# Battery_and_Charging.net
KiCad netlist of a schematic drawn in Altium Designer
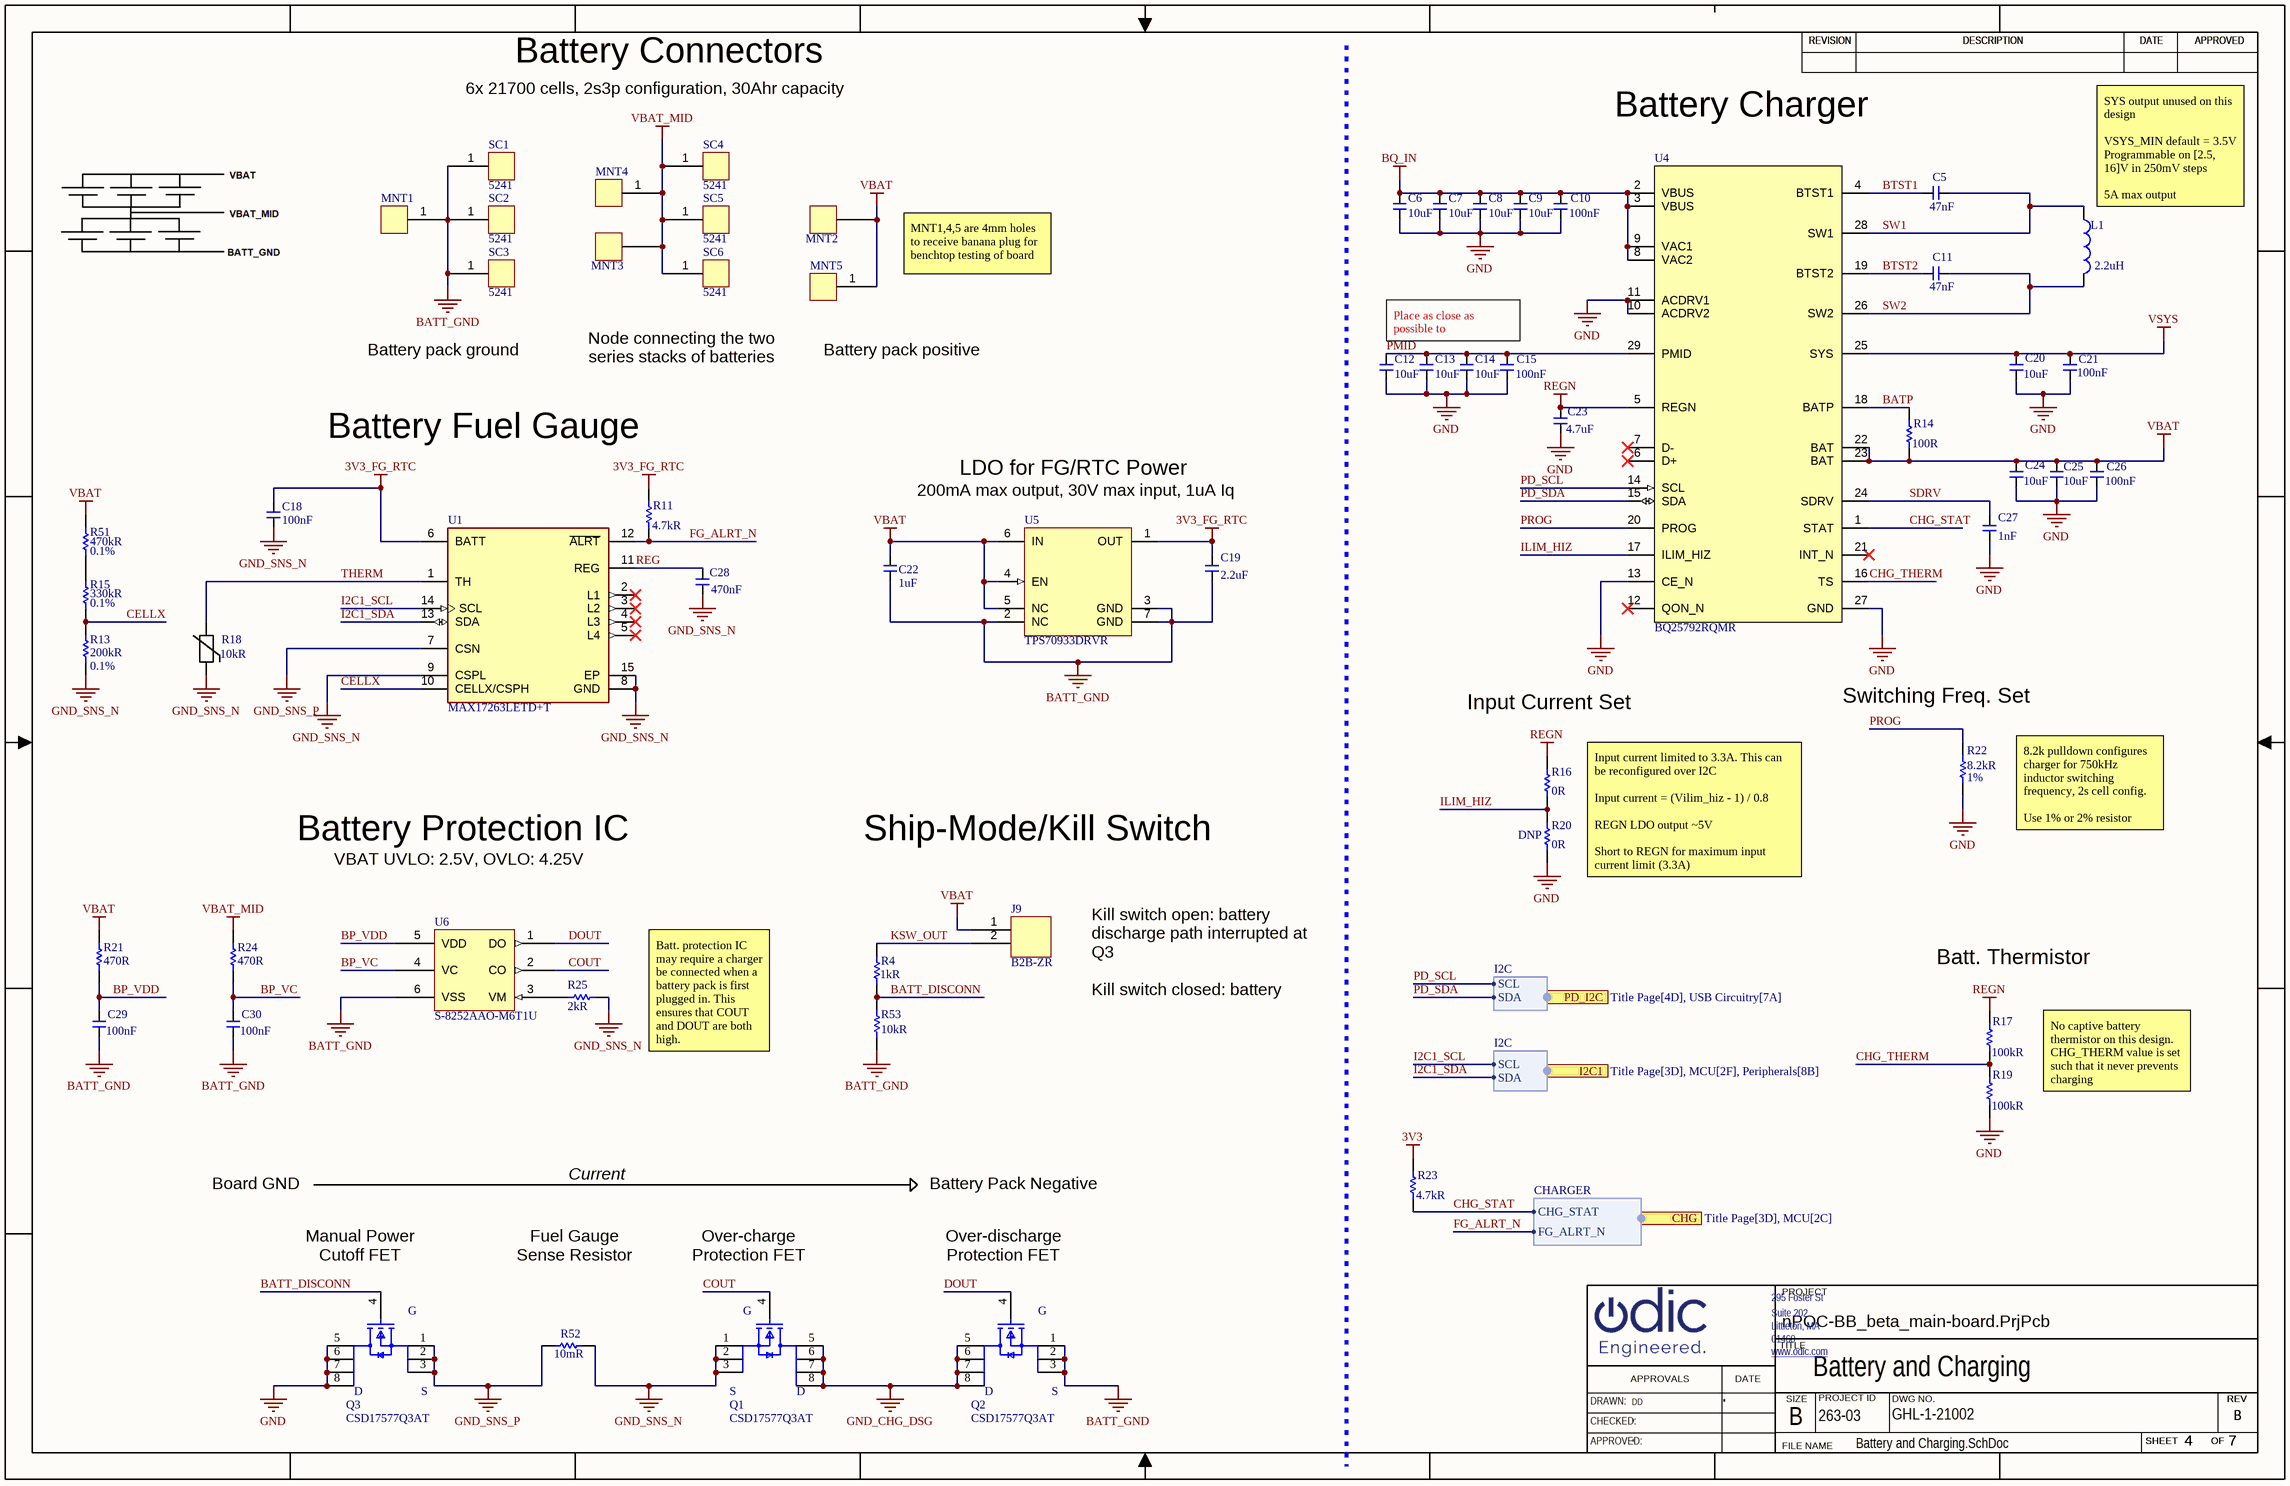
[diagram p0: Battery and Charging.SchDoc]

(export (version "E")
  (design (tool "Eeschema 10.0.6"))
  (components
    (comp (ref "C5")
      (value "C0402_47n_50V_10pct")
      (footprint "C0402")
      (description "CGA2B3X7R1H473K050BB")
      (fields (field (name "TOLERANCE") "10%") (field (name "CAPACITANCE") "47nF"))
      (libsource (lib "Odic Inc") (part "cAP"))
    )
    (comp (ref "C6")
      (value "C0603_10u_25V_10pct")
      (footprint "C0603")
      (description "GRM188R61E106KA73J")
      (fields (field (name "CAPACITANCE") "10uF") (field (name "TOLERANCE") "10%"))
      (libsource (lib "Odic Inc") (part "cAP"))
    )
    (comp (ref "C7")
      (value "C0603_10u_25V_10pct")
      (footprint "C0603")
      (description "GRM188R61E106KA73J")
      (fields (field (name "CAPACITANCE") "10uF") (field (name "TOLERANCE") "10%"))
      (libsource (lib "Odic Inc") (part "cAP"))
    )
    (comp (ref "C8")
      (value "C0603_10u_25V_10pct")
      (footprint "C0603")
      (description "GRM188R61E106KA73J")
      (fields (field (name "CAPACITANCE") "10uF") (field (name "TOLERANCE") "10%"))
      (libsource (lib "Odic Inc") (part "cAP"))
    )
    (comp (ref "C9")
      (value "C0603_10u_25V_10pct")
      (footprint "C0603")
      (description "GRM188R61E106KA73J")
      (fields (field (name "CAPACITANCE") "10uF") (field (name "TOLERANCE") "10%"))
      (libsource (lib "Odic Inc") (part "cAP"))
    )
    (comp (ref "C10")
      (value "C0402_0u1_25V_10pct")
      (footprint "C0402")
      (description "Cap Ceramic 0.1uF 25V X5R 10% Pad SMD 0402 Multi Layer Ceramic Capacitor (MLCC)")
      (fields
        (field (name "VOLTAGE") "25V")
        (field (name "TOLERANCE") "10%")
        (field (name "CAPACITANCE") "100nF")
      )
      (libsource (lib "Odic Inc") (part "cAP"))
    )
    (comp (ref "C11")
      (value "C0402_47n_50V_10pct")
      (footprint "C0402")
      (description "CGA2B3X7R1H473K050BB")
      (fields (field (name "TOLERANCE") "10%") (field (name "CAPACITANCE") "47nF"))
      (libsource (lib "Odic Inc") (part "cAP"))
    )
    (comp (ref "C12")
      (value "C0603_10u_25V_10pct")
      (footprint "C0603")
      (description "GRM188R61E106KA73J")
      (fields (field (name "CAPACITANCE") "10uF") (field (name "TOLERANCE") "10%"))
      (libsource (lib "Odic Inc") (part "cAP"))
    )
    (comp (ref "C13")
      (value "C0603_10u_25V_10pct")
      (footprint "C0603")
      (description "GRM188R61E106KA73J")
      (fields (field (name "CAPACITANCE") "10uF") (field (name "TOLERANCE") "10%"))
      (libsource (lib "Odic Inc") (part "cAP"))
    )
    (comp (ref "C14")
      (value "C0603_10u_25V_10pct")
      (footprint "C0603")
      (description "GRM188R61E106KA73J")
      (fields (field (name "CAPACITANCE") "10uF") (field (name "TOLERANCE") "10%"))
      (libsource (lib "Odic Inc") (part "cAP"))
    )
    (comp (ref "C15")
      (value "C0402_0u1_25V_10pct")
      (footprint "C0402")
      (description "Cap Ceramic 0.1uF 25V X5R 10% Pad SMD 0402 Multi Layer Ceramic Capacitor (MLCC)")
      (fields
        (field (name "VOLTAGE") "25V")
        (field (name "TOLERANCE") "10%")
        (field (name "CAPACITANCE") "100nF")
      )
      (libsource (lib "Odic Inc") (part "cAP"))
    )
    (comp (ref "C18")
      (value "C0402_100n_16V_10pct")
      (footprint "C0402")
      (description "0.1 µF ±10% 16V Ceramic Capacitor X7R 0402 (1005 Metric)")
      (fields
        (field (name "VOLTAGE") "16V")
        (field (name "TOLERANCE") "10%")
        (field (name "CAPACITANCE") "100nF")
      )
      (libsource (lib "Odic Inc") (part "cAP"))
    )
    (comp (ref "C19")
      (value "C0402_2u2_6V3_10pct")
      (footprint "C0402")
      (description "CAP CER 2.2UF 6.3V X5R 0402")
      (fields (field (name "CAPACITANCE") "2.2uF") (field (name "TOLERANCE") "10%"))
      (libsource (lib "Odic Inc") (part "cAP"))
    )
    (comp (ref "C20")
      (value "C0603_10u_25V_10pct")
      (footprint "C0603")
      (description "GRM188R61E106KA73J")
      (fields (field (name "CAPACITANCE") "10uF") (field (name "TOLERANCE") "10%"))
      (libsource (lib "Odic Inc") (part "cAP"))
    )
    (comp (ref "C21")
      (value "C0402_0u1_25V_10pct")
      (footprint "C0402")
      (description "Cap Ceramic 0.1uF 25V X5R 10% Pad SMD 0402 Multi Layer Ceramic Capacitor (MLCC)")
      (fields
        (field (name "VOLTAGE") "25V")
        (field (name "TOLERANCE") "10%")
        (field (name "CAPACITANCE") "100nF")
      )
      (libsource (lib "Odic Inc") (part "cAP"))
    )
    (comp (ref "C22")
      (value "1uF")
      (footprint "C0402")
      (description "CAP CER 1UF 16V X5R 0402")
      (fields (field (name "VOLTAGE") "16V") (field (name "TOLERANCE") "10%"))
      (libsource (lib "Odic Inc") (part "cAP"))
    )
    (comp (ref "C23")
      (value "C0402_4u7_10V_20pct")
      (footprint "C0402")
      (description "Cap Ceramic 4.7uF 10V X5R 20% SMD 0402 85°C Paper T/R")
      (fields (field (name "CAPACITANCE") "4.7uF") (field (name "TOLERANCE") "20%"))
      (libsource (lib "Odic Inc") (part "cAP"))
    )
    (comp (ref "C24")
      (value "C0603_10u_25V_10pct")
      (footprint "C0603")
      (description "GRM188R61E106KA73J")
      (fields (field (name "CAPACITANCE") "10uF") (field (name "TOLERANCE") "10%"))
      (libsource (lib "Odic Inc") (part "cAP"))
    )
    (comp (ref "C25")
      (value "C0603_10u_25V_10pct")
      (footprint "C0603")
      (description "GRM188R61E106KA73J")
      (fields (field (name "CAPACITANCE") "10uF") (field (name "TOLERANCE") "10%"))
      (libsource (lib "Odic Inc") (part "cAP"))
    )
    (comp (ref "C26")
      (value "C0402_0u1_25V_10pct")
      (footprint "C0402")
      (description "Cap Ceramic 0.1uF 25V X5R 10% Pad SMD 0402 Multi Layer Ceramic Capacitor (MLCC)")
      (fields
        (field (name "VOLTAGE") "25V")
        (field (name "TOLERANCE") "10%")
        (field (name "CAPACITANCE") "100nF")
      )
      (libsource (lib "Odic Inc") (part "cAP"))
    )
    (comp (ref "C27")
      (value "C0402_1n_50V_10pct")
      (footprint "C0402")
      (description "0402 1 nF 50V ±10 % Tolerance X7R Surface Mount Multilayer Ceramic Capacitor")
      (fields
        (field (name "TOLERANCE") "10%")
        (field (name "VOLTAGE") "50V")
        (field (name "CAPACITANCE") "1nF")
      )
      (libsource (lib "Odic Inc") (part "cAP"))
    )
    (comp (ref "C28")
      (value "C0402_470n_6V3_10pct")
      (footprint "C0402")
      (description "Ceramic capacitor SMD-0402 470nF /6, 3V X5R# K +-10%, Samsung, RoHS")
      (fields
        (field (name "CAPACITANCE") "470nF")
        (field (name "VOLTAGE") "6.3V")
        (field (name "TOLERANCE") "10%")
      )
      (libsource (lib "Odic Inc") (part "cAP"))
    )
    (comp (ref "C29")
      (value "100nF")
      (footprint "C0402")
      (description "Ceramic capacitor SMD 0402 100nF 16V X7R 10%")
      (fields (field (name "VOLTAGE") "16V") (field (name "TOLERANCE") "10%"))
      (libsource (lib "Odic Inc") (part "cAP"))
    )
    (comp (ref "C30")
      (value "100nF")
      (footprint "C0402")
      (description "Ceramic capacitor SMD 0402 100nF 16V X7R 10%")
      (fields (field (name "VOLTAGE") "16V") (field (name "TOLERANCE") "10%"))
      (libsource (lib "Odic Inc") (part "cAP"))
    )
    (comp (ref "J9")
      (value "B2B-ZR")
      (footprint "jst-b2b-zr")
      (description "Board Connector, 2 Contact(s), 1 Row(s), Male, Straight, Solder Terminal")
      (libsource (lib "Odic Inc") (part "B2B-ZR-Symbol-1"))
    )
    (comp (ref "L1")
      (value "2.2uH")
      (footprint "ind2_5p4x5p2mm")
      (description "FIXED IND 2.2UH 5.8A 29 MOHM")
      (fields (field (name "TOLERANCE") "20%") (field (name "Comment") "0530CDMCCDS-2R2MC"))
      (libsource (lib "Odic Inc") (part "IND"))
    )
    (comp (ref "MNT1")
      (value "Banana Plug Hole")
      (footprint "conn_wire-1_4mm")
      (description "4mm hole to accept banana plug")
      (libsource (lib "Odic Inc") (part "Banana Plug Hole-Symbol-1"))
    )
    (comp (ref "MNT2")
      (value "SOLDER HOLE 10AWG")
      (footprint "conn_wire-1")
      (description "Hole for 10AWG solder connection")
      (libsource (lib "Odic Inc") (part "SOLDER HOLE-Symbol-1"))
    )
    (comp (ref "MNT3")
      (value "SOLDER HOLE 10AWG")
      (footprint "conn_wire-1")
      (description "Hole for 10AWG solder connection")
      (libsource (lib "Odic Inc") (part "SOLDER HOLE-Symbol-1"))
    )
    (comp (ref "MNT4")
      (value "Banana Plug Hole")
      (footprint "conn_wire-1_4mm")
      (description "4mm hole to accept banana plug")
      (libsource (lib "Odic Inc") (part "Banana Plug Hole-Symbol-1"))
    )
    (comp (ref "MNT5")
      (value "Banana Plug Hole")
      (footprint "conn_wire-1_4mm")
      (description "4mm hole to accept banana plug")
      (libsource (lib "Odic Inc") (part "Banana Plug Hole-Symbol-1"))
    )
    (comp (ref "Q1")
      (value "CSD17577Q3AT")
      (footprint "dfn8_3p1x3p25_p65mm")
      (description "30-V, N channel NexFET™ power MOSFET, single SON 3 mm x 3 mm, 6.4 mOhm 8-VSONP -55 to 150")
      (libsource (lib "Odic Inc") (part "CSD17577Q3AT-symbol"))
    )
    (comp (ref "Q2")
      (value "CSD17577Q3AT")
      (footprint "dfn8_3p1x3p25_p65mm")
      (description "30-V, N channel NexFET™ power MOSFET, single SON 3 mm x 3 mm, 6.4 mOhm 8-VSONP -55 to 150")
      (libsource (lib "Odic Inc") (part "CSD17577Q3AT-symbol"))
    )
    (comp (ref "Q3")
      (value "CSD17577Q3AT")
      (footprint "dfn8_3p1x3p25_p65mm")
      (description "30-V, N channel NexFET™ power MOSFET, single SON 3 mm x 3 mm, 6.4 mOhm 8-VSONP -55 to 150")
      (libsource (lib "Odic Inc") (part "CSD17577Q3AT-symbol"))
    )
    (comp (ref "R4")
      (value "R0402_1k0_1pct")
      (footprint "R0402")
      (description "Surface Mount Chip Resistor, Thick Film, RC Series, 1 kohm, 62.5 mW, 1%, 50 V, 0402 [1005 Metric]")
      (fields (field (name "RESISTANCE") "1kR") (field (name "TOLERANCE") "1%"))
      (libsource (lib "Odic Inc") (part "RES"))
    )
    (comp (ref "R11")
      (value "R0402_4k7_1pct")
      (footprint "R0402")
      (description "RES 4.7K OHM 1% 1/16W 0402")
      (fields (field (name "TOLERANCE") "1%") (field (name "RESISTANCE") "4.7kR"))
      (libsource (lib "Odic Inc") (part "RES"))
    )
    (comp (ref "R13")
      (value "200kR")
      (footprint "R0402")
      (description "SMD Chip Resistor, 200 kOhm, ± 0.1%, 63 mW, 0402 [1005 Metric], Thin Film, Precision")
      (fields (field (name "TOLERANCE") "0.1%") (field (name "Comment") "R0402_200k_0.1pct"))
      (libsource (lib "Odic Inc") (part "RES"))
    )
    (comp (ref "R14")
      (value "100R")
      (footprint "R0402")
      (description "Res General Purpose Thick Film 0402 100 Ohm 1% 1/16W ±200ppm/°C Molded SMD Paper T/R")
      (fields (field (name "TOLERANCE") "1%") (field (name "Comment") "R0402_100R_1pct"))
      (libsource (lib "Odic Inc") (part "RES"))
    )
    (comp (ref "R15")
      (value "330kR")
      (footprint "R0402")
      (description "Res, 330K, 0.1W, 0402, Thin Film Rohs Compliant: Yes")
      (fields (field (name "TOLERANCE") "0.1%") (field (name "Comment") "R0402_330k_0p1pct"))
      (libsource (lib "Odic Inc") (part "RES"))
    )
    (comp (ref "R16")
      (value "R0402_0R")
      (footprint "R0402")
      (description "RES 0 OHM JUMPER 1/16W 0402")
      (fields (field (name "RESISTANCE") "0R"))
      (libsource (lib "Odic Inc") (part "RES"))
    )
    (comp (ref "R17")
      (value "R0402_100k_1pct")
      (footprint "R0402")
      (description "Res General Purpose Thick Film 0402 100K Ohm 1% 1/16W ±100ppm/°C Molded SMD Paper T/R")
      (fields (field (name "RESISTANCE") "100kR") (field (name "TOLERANCE") "1%"))
      (libsource (lib "Odic Inc") (part "RES"))
    )
    (comp (ref "R18")
      (value "10kR")
      (footprint "R0603")
      (description "NTC Thermistor 10k 0603 (1608 Metric)")
      (fields (field (name "Comment") "NCU18XH103F6SRB"))
      (libsource (lib "Odic Inc") (part "THERM"))
    )
    (comp (ref "R19")
      (value "R0402_100k_1pct")
      (footprint "R0402")
      (description "Res General Purpose Thick Film 0402 100K Ohm 1% 1/16W ±100ppm/°C Molded SMD Paper T/R")
      (fields (field (name "RESISTANCE") "100kR") (field (name "TOLERANCE") "1%"))
      (libsource (lib "Odic Inc") (part "RES"))
    )
    (comp (ref "R20")
      (value "R0402_0R")
      (footprint "R0402")
      (description "RES 0 OHM JUMPER 1/16W 0402")
      (fields (field (name "INSTALL") "DNP") (field (name "RESISTANCE") "0R"))
      (libsource (lib "Odic Inc") (part "RES"))
    )
    (comp (ref "R21")
      (value "R0402_470R_1pct")
      (footprint "R0402")
      (description "Res Thick Film 0402 470 Ohm 1% 0.063W(1/16W) ±100ppm/C Pad SMD T/R")
      (fields (field (name "TOLERANCE") "1%") (field (name "RESISTANCE") "470R"))
      (libsource (lib "Odic Inc") (part "RES"))
    )
    (comp (ref "R22")
      (value "8.2kR")
      (footprint "R0402")
      (description "SMD Chip Resistor, 8.2 kOhm, ± 1%, 62.5 mW, 0402 [1005 Metric], Thick Film, General Purpose")
      (fields
        (field (name "RESISTANCE TOLERANCE") "1%")
        (field (name "TOLERANCE") "1%")
        (field (name "Comment") "R0402_8k2_1pct")
      )
      (libsource (lib "Odic Inc") (part "RES"))
    )
    (comp (ref "R23")
      (value "R0402_4k7_1pct")
      (footprint "R0402")
      (description "RES 4.7K OHM 1% 1/16W 0402")
      (fields (field (name "TOLERANCE") "1%") (field (name "RESISTANCE") "4.7kR"))
      (libsource (lib "Odic Inc") (part "RES"))
    )
    (comp (ref "R24")
      (value "R0402_470R_1pct")
      (footprint "R0402")
      (description "Res Thick Film 0402 470 Ohm 1% 0.063W(1/16W) ±100ppm/C Pad SMD T/R")
      (fields (field (name "TOLERANCE") "1%") (field (name "RESISTANCE") "470R"))
      (libsource (lib "Odic Inc") (part "RES"))
    )
    (comp (ref "R25")
      (value "R0402_2k_1pct")
      (footprint "R0402")
      (description "Res General Purpose Thick Film 0402 2K Ohm 1% 1/16W ±100ppm/°C Molded SMD Paper T/R")
      (fields (field (name "TOLERANCE") "1%") (field (name "RESISTANCE") "2kR"))
      (libsource (lib "Odic Inc") (part "RES"))
    )
    (comp (ref "R51")
      (value "470kR")
      (footprint "R0402")
      (description "470 kOhms 0.1% 0.063W, 1/16W Chip Resistor 0402 (1005 Metric) Anti-Sulfur, Autom")
      (fields (field (name "TOLERANCE") "0.1%") (field (name "Comment") "R0402_470k_0p1pct"))
      (libsource (lib "Odic Inc") (part "RES"))
    )
    (comp (ref "R52")
      (value "10mR")
      (footprint "R2010")
      (description "Res Current Sense Metal Strip 2010 0.01 Ohm 1% 2W ±75ppm/°C Molded Emboss T/R")
      (fields (field (name "Comment") "R0402_10m_1pct"))
      (libsource (lib "Odic Inc") (part "RES"))
    )
    (comp (ref "R53")
      (value "R0402_10k_1pct")
      (footprint "R0402")
      (description "Res Thick Film 0402 10K Ohm 1% 1/16W ±100ppm/°C Molded SMD SMD T/R")
      (fields (field (name "RESISTANCE") "10kR") (field (name "TOLERANCE") "1%"))
      (libsource (lib "Odic Inc") (part "RES"))
    )
    (comp (ref "SC1")
      (value "5241")
      (footprint "bat_keystone-5241")
      (description "Cylindrical Battery Contacts, Clips, Holders & Springs C Cell Negative Battery Contact")
      (libsource (lib "Odic Inc") (part "5241-Symbol-1"))
    )
    (comp (ref "SC2")
      (value "5241")
      (footprint "bat_keystone-5241")
      (description "Cylindrical Battery Contacts, Clips, Holders & Springs C Cell Negative Battery Contact")
      (libsource (lib "Odic Inc") (part "5241-Symbol-1"))
    )
    (comp (ref "SC3")
      (value "5241")
      (footprint "bat_keystone-5241")
      (description "Cylindrical Battery Contacts, Clips, Holders & Springs C Cell Negative Battery Contact")
      (libsource (lib "Odic Inc") (part "5241-Symbol-1"))
    )
    (comp (ref "SC4")
      (value "5241")
      (footprint "bat_keystone-5241")
      (description "Cylindrical Battery Contacts, Clips, Holders & Springs C Cell Negative Battery Contact")
      (libsource (lib "Odic Inc") (part "5241-Symbol-1"))
    )
    (comp (ref "SC5")
      (value "5241")
      (footprint "bat_keystone-5241")
      (description "Cylindrical Battery Contacts, Clips, Holders & Springs C Cell Negative Battery Contact")
      (libsource (lib "Odic Inc") (part "5241-Symbol-1"))
    )
    (comp (ref "SC6")
      (value "5241")
      (footprint "bat_keystone-5241")
      (description "Cylindrical Battery Contacts, Clips, Holders & Springs C Cell Negative Battery Contact")
      (libsource (lib "Odic Inc") (part "5241-Symbol-1"))
    )
    (comp (ref "U1")
      (value "MAX17263LETD+T")
      (footprint "dfn14_3x3_p4mm")
      (description "MAX17263 Series 4.9 V Single/Multi-Cell Ultra-Low Power Fuel-Gauge IC-TDFN-14EP")
      (libsource (lib "Odic Inc") (part "9e6c63fd24431d9ce7a831344c264e3"))
    )
    (comp (ref "U4")
      (value "BQ25792RQMR")
      (footprint "qfn29_4x4_p4mm-RQM0029A")
      (description "I2C Controlled, 1-4 Cell, 5-A Buck-Boost Battery Charger with Dual-Input")
      (libsource (lib "Odic Inc") (part "PQ25792RQMR"))
    )
    (comp (ref "U5")
      (value "TPS70933DRVR")
      (footprint "dfn7_2x2_p65mm")
      (description "LDO Regulator Positive 3.3V 0.15A 6-Pin SON T/R")
      (libsource (lib "Odic Inc") (part "TPS70933DRVR-symbol"))
    )
    (comp (ref "U6")
      (value "S-8252AAO-M6T1U")
      (footprint "SOT23-6PIN")
      (description "Battery Protection Li-Ion/Li-Pol 6-Pin SOT-23 T/R. 4.25V OVP, 2.5V UVP")
      (libsource (lib "Odic Inc") (part "S-8252AAO-M6T1U-Symbol-1"))
    )
  )
  (nets
    (net (code "3") (name "/BATP") (class "Default")
      (node (ref "R14") (pin "2") (pinfunction "2_2") (pintype "passive"))
      (node (ref "U4") (pin "18") (pinfunction "BATP_18") (pintype "passive"))
    )
    (net (code "4") (name "/BATT_DISCONN") (class "Default")
      (node (ref "Q3") (pin "4") (pinfunction "G_4") (pintype "passive"))
      (node (ref "R4") (pin "1") (pinfunction "1_1") (pintype "passive"))
      (node (ref "R53") (pin "2") (pinfunction "2_2") (pintype "passive"))
    )
    (net (code "5") (name "/BP_VC") (class "Default")
      (node (ref "C30") (pin "2") (pinfunction "2_2") (pintype "passive"))
      (node (ref "R24") (pin "2") (pinfunction "2_2") (pintype "passive"))
      (node (ref "U6") (pin "4") (pinfunction "VC_4") (pintype "passive"))
    )
    (net (code "6") (name "/BP_VDD") (class "Default")
      (node (ref "C29") (pin "2") (pinfunction "2_2") (pintype "passive"))
      (node (ref "R21") (pin "2") (pinfunction "2_2") (pintype "passive"))
      (node (ref "U6") (pin "5") (pinfunction "VDD_5") (pintype "passive"))
    )
    (net (code "7") (name "/BTST1") (class "Default")
      (node (ref "C5") (pin "2") (pinfunction "2_2") (pintype "passive"))
      (node (ref "U4") (pin "4") (pinfunction "BTST1_4") (pintype "passive"))
    )
    (net (code "8") (name "/BTST2") (class "Default")
      (node (ref "C11") (pin "2") (pinfunction "2_2") (pintype "passive"))
      (node (ref "U4") (pin "19") (pinfunction "BTST2_19") (pintype "passive"))
    )
    (net (code "9") (name "/CELLX") (class "Default")
      (node (ref "R13") (pin "1") (pinfunction "1_1") (pintype "passive"))
      (node (ref "R15") (pin "1") (pinfunction "1_1") (pintype "passive"))
      (node (ref "U1") (pin "10") (pinfunction "CELLX/CSPH_10") (pintype "passive"))
    )
    (net (code "10") (name "/CHG_STAT") (class "Default")
      (node (ref "R23") (pin "1") (pinfunction "1_1") (pintype "passive"))
      (node (ref "U4") (pin "1") (pinfunction "STAT_1") (pintype "passive"))
    )
    (net (code "11") (name "/CHG_THERM") (class "Default")
      (node (ref "R17") (pin "1") (pinfunction "1_1") (pintype "passive"))
      (node (ref "R19") (pin "2") (pinfunction "2_2") (pintype "passive"))
      (node (ref "U4") (pin "16") (pinfunction "TS_16") (pintype "passive"))
    )
    (net (code "12") (name "/COUT") (class "Default")
      (node (ref "Q1") (pin "4") (pinfunction "G_4") (pintype "passive"))
      (node (ref "U6") (pin "2") (pinfunction "CO_2") (pintype "output"))
    )
    (net (code "13") (name "/DOUT") (class "Default")
      (node (ref "Q2") (pin "4") (pinfunction "G_4") (pintype "passive"))
      (node (ref "U6") (pin "1") (pinfunction "DO_1") (pintype "output"))
    )
    (net (code "14") (name "/FG_ALRT_N") (class "Default")
      (node (ref "R11") (pin "1") (pinfunction "1_1") (pintype "passive"))
      (node (ref "U1") (pin "12") (pinfunction "~{ALRT}_12") (pintype "open_collector"))
    )
    (net (code "15") (name "/I2C1_SCL") (class "Default")
      (node (ref "U1") (pin "14") (pinfunction "SCL_14") (pintype "input"))
    )
    (net (code "16") (name "/I2C1_SDA") (class "Default")
      (node (ref "U1") (pin "13") (pinfunction "SDA_13") (pintype "bidirectional"))
    )
    (net (code "17") (name "/ILIM_HIZ") (class "Default")
      (node (ref "R16") (pin "1") (pinfunction "1_1") (pintype "passive"))
      (node (ref "R20") (pin "2") (pinfunction "2_2") (pintype "passive"))
      (node (ref "U4") (pin "17") (pinfunction "ILIM_HIZ_17") (pintype "passive"))
    )
    (net (code "18") (name "/KSW_OUT") (class "Default")
      (node (ref "J9") (pin "2") (pinfunction "2_2") (pintype "passive"))
      (node (ref "R4") (pin "2") (pinfunction "2_2") (pintype "passive"))
    )
    (net (code "19") (name "/PD_SCL") (class "Default")
      (node (ref "U4") (pin "14") (pinfunction "SCL_14") (pintype "input"))
    )
    (net (code "20") (name "/PD_SDA") (class "Default")
      (node (ref "U4") (pin "15") (pinfunction "SDA_15") (pintype "bidirectional"))
    )
    (net (code "21") (name "/PMID") (class "Default")
      (node (ref "C12") (pin "2") (pinfunction "2_2") (pintype "passive"))
      (node (ref "C13") (pin "2") (pinfunction "2_2") (pintype "passive"))
      (node (ref "C14") (pin "2") (pinfunction "2_2") (pintype "passive"))
      (node (ref "C15") (pin "2") (pinfunction "2_2") (pintype "passive"))
      (node (ref "U4") (pin "29") (pinfunction "PMID_29") (pintype "passive"))
    )
    (net (code "22") (name "/PROG") (class "Default")
      (node (ref "R22") (pin "2") (pinfunction "2_2") (pintype "passive"))
      (node (ref "U4") (pin "20") (pinfunction "PROG_20") (pintype "passive"))
    )
    (net (code "23") (name "/REG") (class "Default")
      (node (ref "C28") (pin "2") (pinfunction "2_2") (pintype "passive"))
      (node (ref "U1") (pin "11") (pinfunction "REG_11") (pintype "power_in"))
    )
    (net (code "24") (name "/SDRV") (class "Default")
      (node (ref "C27") (pin "2") (pinfunction "2_2") (pintype "passive"))
      (node (ref "U4") (pin "24") (pinfunction "SDRV_24") (pintype "passive"))
    )
    (net (code "25") (name "/SW1") (class "Default")
      (node (ref "C5") (pin "1") (pinfunction "1_1") (pintype "passive"))
      (node (ref "L1") (pin "1") (pinfunction "1_1") (pintype "passive"))
      (node (ref "U4") (pin "28") (pinfunction "SW1_28") (pintype "passive"))
    )
    (net (code "26") (name "/SW2") (class "Default")
      (node (ref "C11") (pin "1") (pinfunction "1_1") (pintype "passive"))
      (node (ref "L1") (pin "2") (pinfunction "2_2") (pintype "passive"))
      (node (ref "U4") (pin "26") (pinfunction "SW2_26") (pintype "passive"))
    )
    (net (code "27") (name "/THERM") (class "Default")
      (node (ref "R18") (pin "2") (pinfunction "2_2") (pintype "passive"))
      (node (ref "U1") (pin "1") (pinfunction "TH_1") (pintype "passive"))
    )
    (net (code "30") (name "3V3") (class "Default")
      (node (ref "R23") (pin "2") (pinfunction "2_2") (pintype "passive"))
    )
    (net (code "31") (name "3V3_FG_RTC") (class "Default")
      (node (ref "C18") (pin "1") (pinfunction "1_1") (pintype "passive"))
      (node (ref "C19") (pin "2") (pinfunction "2_2") (pintype "passive"))
      (node (ref "R11") (pin "2") (pinfunction "2_2") (pintype "passive"))
      (node (ref "U1") (pin "6") (pinfunction "BATT_6") (pintype "power_in"))
      (node (ref "U5") (pin "1") (pinfunction "OUT_1") (pintype "power_in"))
    )
    (net (code "32") (name "BATT_GND") (class "Default")
      (node (ref "C19") (pin "1") (pinfunction "1_1") (pintype "passive"))
      (node (ref "C22") (pin "1") (pinfunction "1_1") (pintype "passive"))
      (node (ref "C29") (pin "1") (pinfunction "1_1") (pintype "passive"))
      (node (ref "C30") (pin "1") (pinfunction "1_1") (pintype "passive"))
      (node (ref "MNT1") (pin "1") (pinfunction "1_1") (pintype "passive"))
      (node (ref "Q2") (pin "1") (pinfunction "S_1") (pintype "passive"))
      (node (ref "Q2") (pin "2") (pinfunction "S_2") (pintype "passive"))
      (node (ref "Q2") (pin "3") (pinfunction "S_3") (pintype "passive"))
      (node (ref "R53") (pin "1") (pinfunction "1_1") (pintype "passive"))
      (node (ref "SC1") (pin "1") (pinfunction "1_1") (pintype "passive"))
      (node (ref "SC2") (pin "1") (pinfunction "1_1") (pintype "passive"))
      (node (ref "SC3") (pin "1") (pinfunction "1_1") (pintype "passive"))
      (node (ref "U5") (pin "2") (pinfunction "NC_2") (pintype "passive"))
      (node (ref "U5") (pin "3") (pinfunction "GND_3") (pintype "power_in"))
      (node (ref "U5") (pin "7") (pinfunction "GND_7") (pintype "power_in"))
      (node (ref "U6") (pin "6") (pinfunction "VSS_6") (pintype "passive"))
    )
    (net (code "33") (name "BQ_IN") (class "Default")
      (node (ref "C10") (pin "2") (pinfunction "2_2") (pintype "passive"))
      (node (ref "C6") (pin "2") (pinfunction "2_2") (pintype "passive"))
      (node (ref "C7") (pin "2") (pinfunction "2_2") (pintype "passive"))
      (node (ref "C8") (pin "2") (pinfunction "2_2") (pintype "passive"))
      (node (ref "C9") (pin "2") (pinfunction "2_2") (pintype "passive"))
      (node (ref "U4") (pin "2") (pinfunction "VBUS_2") (pintype "power_in"))
      (node (ref "U4") (pin "3") (pinfunction "VBUS_3") (pintype "power_in"))
      (node (ref "U4") (pin "8") (pinfunction "VAC2_8") (pintype "power_in"))
      (node (ref "U4") (pin "9") (pinfunction "VAC1_9") (pintype "power_in"))
    )
    (net (code "34") (name "GND") (class "Default")
      (node (ref "C10") (pin "1") (pinfunction "1_1") (pintype "passive"))
      (node (ref "C12") (pin "1") (pinfunction "1_1") (pintype "passive"))
      (node (ref "C13") (pin "1") (pinfunction "1_1") (pintype "passive"))
      (node (ref "C14") (pin "1") (pinfunction "1_1") (pintype "passive"))
      (node (ref "C15") (pin "1") (pinfunction "1_1") (pintype "passive"))
      (node (ref "C20") (pin "1") (pinfunction "1_1") (pintype "passive"))
      (node (ref "C21") (pin "1") (pinfunction "1_1") (pintype "passive"))
      (node (ref "C23") (pin "1") (pinfunction "1_1") (pintype "passive"))
      (node (ref "C24") (pin "1") (pinfunction "1_1") (pintype "passive"))
      (node (ref "C25") (pin "1") (pinfunction "1_1") (pintype "passive"))
      (node (ref "C26") (pin "1") (pinfunction "1_1") (pintype "passive"))
      (node (ref "C27") (pin "1") (pinfunction "1_1") (pintype "passive"))
      (node (ref "C6") (pin "1") (pinfunction "1_1") (pintype "passive"))
      (node (ref "C7") (pin "1") (pinfunction "1_1") (pintype "passive"))
      (node (ref "C8") (pin "1") (pinfunction "1_1") (pintype "passive"))
      (node (ref "C9") (pin "1") (pinfunction "1_1") (pintype "passive"))
      (node (ref "Q3") (pin "5") (pinfunction "D_5") (pintype "passive"))
      (node (ref "Q3") (pin "6") (pinfunction "D_6") (pintype "passive"))
      (node (ref "Q3") (pin "7") (pinfunction "D_7") (pintype "passive"))
      (node (ref "Q3") (pin "8") (pinfunction "D_8") (pintype "passive"))
      (node (ref "R19") (pin "1") (pinfunction "1_1") (pintype "passive"))
      (node (ref "R20") (pin "1") (pinfunction "1_1") (pintype "passive"))
      (node (ref "R22") (pin "1") (pinfunction "1_1") (pintype "passive"))
      (node (ref "U4") (pin "10") (pinfunction "ACDRV2_10") (pintype "power_in"))
      (node (ref "U4") (pin "11") (pinfunction "ACDRV1_11") (pintype "power_in"))
      (node (ref "U4") (pin "13") (pinfunction "CE_N_13") (pintype "passive"))
      (node (ref "U4") (pin "27") (pinfunction "GND_27") (pintype "power_in"))
    )
    (net (code "35") (name "GND_CHG_DSG") (class "Default")
      (node (ref "Q1") (pin "5") (pinfunction "D_5") (pintype "passive"))
      (node (ref "Q1") (pin "6") (pinfunction "D_6") (pintype "passive"))
      (node (ref "Q1") (pin "7") (pinfunction "D_7") (pintype "passive"))
      (node (ref "Q1") (pin "8") (pinfunction "D_8") (pintype "passive"))
      (node (ref "Q2") (pin "5") (pinfunction "D_5") (pintype "passive"))
      (node (ref "Q2") (pin "6") (pinfunction "D_6") (pintype "passive"))
      (node (ref "Q2") (pin "7") (pinfunction "D_7") (pintype "passive"))
      (node (ref "Q2") (pin "8") (pinfunction "D_8") (pintype "passive"))
    )
    (net (code "36") (name "GND_SNS_N") (class "Default")
      (node (ref "C18") (pin "2") (pinfunction "2_2") (pintype "passive"))
      (node (ref "C28") (pin "1") (pinfunction "1_1") (pintype "passive"))
      (node (ref "Q1") (pin "1") (pinfunction "S_1") (pintype "passive"))
      (node (ref "Q1") (pin "2") (pinfunction "S_2") (pintype "passive"))
      (node (ref "Q1") (pin "3") (pinfunction "S_3") (pintype "passive"))
      (node (ref "R13") (pin "2") (pinfunction "2_2") (pintype "passive"))
      (node (ref "R18") (pin "1") (pinfunction "1_1") (pintype "passive"))
      (node (ref "R25") (pin "2") (pinfunction "2_2") (pintype "passive"))
      (node (ref "R52") (pin "2") (pinfunction "2_2") (pintype "passive"))
      (node (ref "U1") (pin "15") (pinfunction "EP_15") (pintype "power_in"))
      (node (ref "U1") (pin "8") (pinfunction "GND_8") (pintype "power_in"))
      (node (ref "U1") (pin "9") (pinfunction "CSPL_9") (pintype "passive"))
    )
    (net (code "37") (name "GND_SNS_P") (class "Default")
      (node (ref "Q3") (pin "1") (pinfunction "S_1") (pintype "passive"))
      (node (ref "Q3") (pin "2") (pinfunction "S_2") (pintype "passive"))
      (node (ref "Q3") (pin "3") (pinfunction "S_3") (pintype "passive"))
      (node (ref "R52") (pin "1") (pinfunction "1_1") (pintype "passive"))
      (node (ref "U1") (pin "7") (pinfunction "CSN_7") (pintype "passive"))
    )
    (net (code "38") (name "Net-(R15-Pad2)") (class "Default")
      (node (ref "R15") (pin "2") (pinfunction "2_2") (pintype "passive"))
      (node (ref "R51") (pin "1") (pinfunction "1_1") (pintype "passive"))
    )
    (net (code "39") (name "Net-(U6-VM)") (class "Default")
      (node (ref "R25") (pin "1") (pinfunction "1_1") (pintype "passive"))
      (node (ref "U6") (pin "3") (pinfunction "VM_3") (pintype "input"))
    )
    (net (code "40") (name "REGN") (class "Default")
      (node (ref "C23") (pin "2") (pinfunction "2_2") (pintype "passive"))
      (node (ref "R16") (pin "2") (pinfunction "2_2") (pintype "passive"))
      (node (ref "R17") (pin "2") (pinfunction "2_2") (pintype "passive"))
      (node (ref "U4") (pin "5") (pinfunction "REGN_5") (pintype "passive"))
    )
    (net (code "41") (name "VBAT") (class "Default")
      (node (ref "C22") (pin "2") (pinfunction "2_2") (pintype "passive"))
      (node (ref "C24") (pin "2") (pinfunction "2_2") (pintype "passive"))
      (node (ref "C25") (pin "2") (pinfunction "2_2") (pintype "passive"))
      (node (ref "C26") (pin "2") (pinfunction "2_2") (pintype "passive"))
      (node (ref "J9") (pin "1") (pinfunction "1_1") (pintype "passive"))
      (node (ref "MNT2") (pin "1") (pinfunction "1_1") (pintype "passive"))
      (node (ref "MNT5") (pin "1") (pinfunction "1_1") (pintype "passive"))
      (node (ref "R14") (pin "1") (pinfunction "1_1") (pintype "passive"))
      (node (ref "R21") (pin "1") (pinfunction "1_1") (pintype "passive"))
      (node (ref "R51") (pin "2") (pinfunction "2_2") (pintype "passive"))
      (node (ref "U4") (pin "22") (pinfunction "BAT_22") (pintype "passive"))
      (node (ref "U4") (pin "23") (pinfunction "BAT_23") (pintype "passive"))
      (node (ref "U5") (pin "4") (pinfunction "EN_4") (pintype "input"))
      (node (ref "U5") (pin "5") (pinfunction "NC_5") (pintype "passive"))
      (node (ref "U5") (pin "6") (pinfunction "IN_6") (pintype "power_in"))
    )
    (net (code "42") (name "VBAT_MID") (class "Default")
      (node (ref "MNT3") (pin "1") (pinfunction "1_1") (pintype "passive"))
      (node (ref "MNT4") (pin "1") (pinfunction "1_1") (pintype "passive"))
      (node (ref "R24") (pin "1") (pinfunction "1_1") (pintype "passive"))
      (node (ref "SC4") (pin "1") (pinfunction "1_1") (pintype "passive"))
      (node (ref "SC5") (pin "1") (pinfunction "1_1") (pintype "passive"))
      (node (ref "SC6") (pin "1") (pinfunction "1_1") (pintype "passive"))
    )
    (net (code "43") (name "VSYS") (class "Default")
      (node (ref "C20") (pin "2") (pinfunction "2_2") (pintype "passive"))
      (node (ref "C21") (pin "2") (pinfunction "2_2") (pintype "passive"))
      (node (ref "U4") (pin "25") (pinfunction "SYS_25") (pintype "passive"))
    )
    (net (code "44") (name "unconnected-(U1-L1-Pad2)") (class "Default")
      (node (ref "U1") (pin "2") (pinfunction "L1_2") (pintype "output+no_connect"))
    )
    (net (code "45") (name "unconnected-(U1-L2-Pad3)") (class "Default")
      (node (ref "U1") (pin "3") (pinfunction "L2_3") (pintype "output+no_connect"))
    )
    (net (code "46") (name "unconnected-(U1-L3-Pad4)") (class "Default")
      (node (ref "U1") (pin "4") (pinfunction "L3_4") (pintype "output+no_connect"))
    )
    (net (code "47") (name "unconnected-(U1-L4-Pad5)") (class "Default")
      (node (ref "U1") (pin "5") (pinfunction "L4_5") (pintype "output+no_connect"))
    )
    (net (code "48") (name "unconnected-(U4-D+-Pad6)") (class "Default")
      (node (ref "U4") (pin "6") (pinfunction "D+_6") (pintype "passive+no_connect"))
    )
    (net (code "49") (name "unconnected-(U4-D--Pad7)") (class "Default")
      (node (ref "U4") (pin "7") (pinfunction "D-_7") (pintype "passive+no_connect"))
    )
    (net (code "50") (name "unconnected-(U4-INT_N-Pad21)") (class "Default")
      (node (ref "U4") (pin "21") (pinfunction "INT_N_21") (pintype "passive+no_connect"))
    )
    (net (code "51") (name "unconnected-(U4-QON_N-Pad12)") (class "Default")
      (node (ref "U4") (pin "12") (pinfunction "QON_N_12") (pintype "passive+no_connect"))
    )
  )
)
